# ECU_Sheet6.net
KiCad netlist of a schematic drawn in Altium Designer
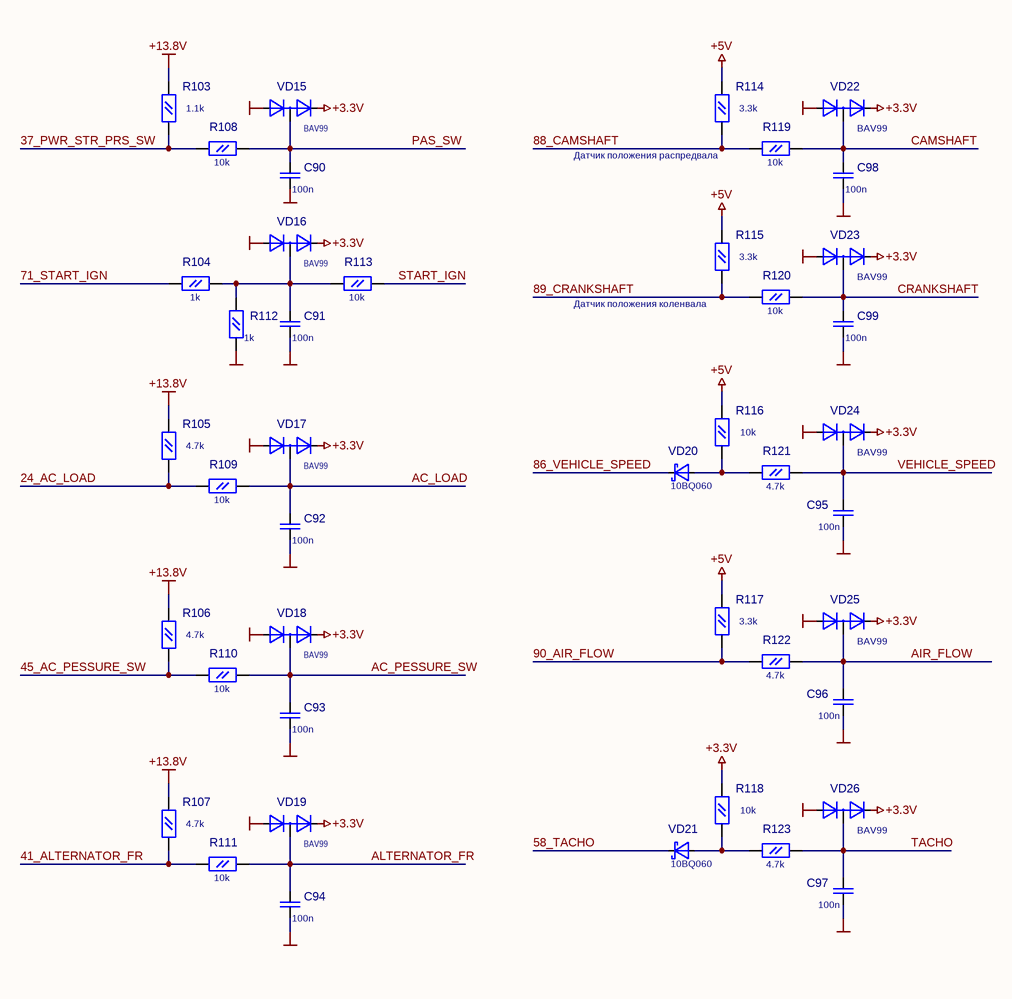
[diagram p0: ECU_Sheet6.SchDoc]

(export (version "E")
  (design (tool "Eeschema 10.0.6"))
  (components
    (comp (ref "C90")
      (value "100n")
      (footprint "C0805L")
      (description "C0603")
      (fields (field (name "Comment") "CSMD"))
      (libsource (lib "L1") (part "CSMD"))
    )
    (comp (ref "C91")
      (value "100n")
      (footprint "C0805L")
      (description "C0603")
      (fields (field (name "Comment") "CSMD"))
      (libsource (lib "L1") (part "CSMD"))
    )
    (comp (ref "C92")
      (value "100n")
      (footprint "C0805L")
      (description "C0603")
      (fields (field (name "Comment") "CSMD"))
      (libsource (lib "L1") (part "CSMD"))
    )
    (comp (ref "C93")
      (value "100n")
      (footprint "C0805L")
      (description "C0603")
      (fields (field (name "Comment") "CSMD"))
      (libsource (lib "L1") (part "CSMD"))
    )
    (comp (ref "C94")
      (value "100n")
      (footprint "C0805L")
      (description "C0603")
      (fields (field (name "Comment") "CSMD"))
      (libsource (lib "L1") (part "CSMD"))
    )
    (comp (ref "C95")
      (value "100n")
      (footprint "C0805L")
      (description "C0603")
      (fields (field (name "Comment") "CSMD"))
      (libsource (lib "L1") (part "CSMD"))
    )
    (comp (ref "C96")
      (value "100n")
      (footprint "C0805L")
      (description "C0603")
      (fields (field (name "Comment") "CSMD"))
      (libsource (lib "L1") (part "CSMD"))
    )
    (comp (ref "C97")
      (value "100n")
      (footprint "C0805L")
      (description "C0603")
      (fields (field (name "Comment") "CSMD"))
      (libsource (lib "L1") (part "CSMD"))
    )
    (comp (ref "C98")
      (value "100n")
      (footprint "C0805L")
      (description "C0603")
      (fields (field (name "Comment") "CSMD"))
      (libsource (lib "L1") (part "CSMD"))
    )
    (comp (ref "C99")
      (value "100n")
      (footprint "C0805L")
      (description "C0603")
      (fields (field (name "Comment") "CSMD"))
      (libsource (lib "L1") (part "CSMD"))
    )
    (comp (ref "R103")
      (value "1.1k")
      (footprint "R0805L")
      (description "R0805")
      (fields (field (name "Comment") "RSMD"))
      (libsource (lib "L1") (part "RSMD"))
    )
    (comp (ref "R104")
      (value "1k")
      (footprint "R0805L")
      (description "R0805")
      (fields (field (name "Comment") "RSMD"))
      (libsource (lib "L1") (part "RSMD"))
    )
    (comp (ref "R105")
      (value "4.7k")
      (footprint "R0805L")
      (description "R0805")
      (fields (field (name "Comment") "RSMD"))
      (libsource (lib "L1") (part "RSMD"))
    )
    (comp (ref "R106")
      (value "4.7k")
      (footprint "R0805L")
      (description "R0805")
      (fields (field (name "Comment") "RSMD"))
      (libsource (lib "L1") (part "RSMD"))
    )
    (comp (ref "R107")
      (value "4.7k")
      (footprint "R0805L")
      (description "R0805")
      (fields (field (name "Comment") "RSMD"))
      (libsource (lib "L1") (part "RSMD"))
    )
    (comp (ref "R108")
      (value "10k")
      (footprint "R0805L")
      (description "R0805")
      (fields (field (name "Comment") "RSMD"))
      (libsource (lib "L1") (part "RSMD"))
    )
    (comp (ref "R109")
      (value "10k")
      (footprint "R0805L")
      (description "R0805")
      (fields (field (name "Comment") "RSMD"))
      (libsource (lib "L1") (part "RSMD"))
    )
    (comp (ref "R110")
      (value "10k")
      (footprint "R0805L")
      (description "R0805")
      (fields (field (name "Comment") "RSMD"))
      (libsource (lib "L1") (part "RSMD"))
    )
    (comp (ref "R111")
      (value "10k")
      (footprint "R0805L")
      (description "R0805")
      (fields (field (name "Comment") "RSMD"))
      (libsource (lib "L1") (part "RSMD"))
    )
    (comp (ref "R112")
      (value "1k")
      (footprint "R0805L")
      (description "R0805")
      (fields (field (name "Comment") "RSMD"))
      (libsource (lib "L1") (part "RSMD"))
    )
    (comp (ref "R113")
      (value "10k")
      (footprint "R0805L")
      (description "R0805")
      (fields (field (name "Comment") "RSMD"))
      (libsource (lib "L1") (part "RSMD"))
    )
    (comp (ref "R114")
      (value "3.3k")
      (footprint "R0805L")
      (description "R0805")
      (fields (field (name "Comment") "RSMD"))
      (libsource (lib "L1") (part "RSMD"))
    )
    (comp (ref "R115")
      (value "3.3k")
      (footprint "R0805L")
      (description "R0805")
      (fields (field (name "Comment") "RSMD"))
      (libsource (lib "L1") (part "RSMD"))
    )
    (comp (ref "R116")
      (value "10k")
      (footprint "R0805L")
      (description "R0805")
      (fields (field (name "Comment") "RSMD"))
      (libsource (lib "L1") (part "RSMD"))
    )
    (comp (ref "R117")
      (value "3.3k")
      (footprint "R0805L")
      (description "R0805")
      (fields (field (name "Comment") "RSMD"))
      (libsource (lib "L1") (part "RSMD"))
    )
    (comp (ref "R118")
      (value "10k")
      (footprint "R0805L")
      (description "R0805")
      (fields (field (name "Comment") "RSMD"))
      (libsource (lib "L1") (part "RSMD"))
    )
    (comp (ref "R119")
      (value "10k")
      (footprint "R0805L")
      (description "R0805")
      (fields (field (name "Comment") "RSMD"))
      (libsource (lib "L1") (part "RSMD"))
    )
    (comp (ref "R120")
      (value "10k")
      (footprint "R0805L")
      (description "R0805")
      (fields (field (name "Comment") "RSMD"))
      (libsource (lib "L1") (part "RSMD"))
    )
    (comp (ref "R121")
      (value "4.7k")
      (footprint "R0805L")
      (description "R0805")
      (fields (field (name "Comment") "RSMD"))
      (libsource (lib "L1") (part "RSMD"))
    )
    (comp (ref "R122")
      (value "4.7k")
      (footprint "R0805L")
      (description "R0805")
      (fields (field (name "Comment") "RSMD"))
      (libsource (lib "L1") (part "RSMD"))
    )
    (comp (ref "R123")
      (value "4.7k")
      (footprint "R0805L")
      (description "R0805")
      (fields (field (name "Comment") "RSMD"))
      (libsource (lib "L1") (part "RSMD"))
    )
    (comp (ref "VD15") (value "BAV99") (footprint "SOT-23") (libsource (lib "RL1") (part "BAV99")))
    (comp (ref "VD16") (value "BAV99") (footprint "SOT-23") (libsource (lib "RL1") (part "BAV99")))
    (comp (ref "VD17") (value "BAV99") (footprint "SOT-23") (libsource (lib "RL1") (part "BAV99")))
    (comp (ref "VD18") (value "BAV99") (footprint "SOT-23") (libsource (lib "RL1") (part "BAV99")))
    (comp (ref "VD19") (value "BAV99") (footprint "SOT-23") (libsource (lib "RL1") (part "BAV99")))
    (comp (ref "VD20")
      (value "10BQ060")
      (footprint "RL1:DO-214AA SMB")
      (libsource (lib "RL1") (part "10BQ060"))
    )
    (comp (ref "VD21")
      (value "10BQ060")
      (footprint "RL1:DO-214AA SMB")
      (libsource (lib "RL1") (part "10BQ060"))
    )
    (comp (ref "VD22") (value "BAV99") (footprint "SOT-23") (libsource (lib "RL1") (part "BAV99")))
    (comp (ref "VD23") (value "BAV99") (footprint "SOT-23") (libsource (lib "RL1") (part "BAV99")))
    (comp (ref "VD24") (value "BAV99") (footprint "SOT-23") (libsource (lib "RL1") (part "BAV99")))
    (comp (ref "VD25") (value "BAV99") (footprint "SOT-23") (libsource (lib "RL1") (part "BAV99")))
    (comp (ref "VD26") (value "BAV99") (footprint "SOT-23") (libsource (lib "RL1") (part "BAV99")))
  )
  (nets
    (net (code "1") (name "+3.3V") (class "Default")
      (node (ref "R118") (pin "2") (pinfunction "Pin2_2") (pintype "passive"))
      (node (ref "VD15") (pin "2") (pinfunction "K_2") (pintype "passive"))
      (node (ref "VD16") (pin "2") (pinfunction "K_2") (pintype "passive"))
      (node (ref "VD17") (pin "2") (pinfunction "K_2") (pintype "passive"))
      (node (ref "VD18") (pin "2") (pinfunction "K_2") (pintype "passive"))
      (node (ref "VD19") (pin "2") (pinfunction "K_2") (pintype "passive"))
      (node (ref "VD22") (pin "2") (pinfunction "K_2") (pintype "passive"))
      (node (ref "VD23") (pin "2") (pinfunction "K_2") (pintype "passive"))
      (node (ref "VD24") (pin "2") (pinfunction "K_2") (pintype "passive"))
      (node (ref "VD25") (pin "2") (pinfunction "K_2") (pintype "passive"))
      (node (ref "VD26") (pin "2") (pinfunction "K_2") (pintype "passive"))
    )
    (net (code "2") (name "+5V") (class "Default")
      (node (ref "R114") (pin "2") (pinfunction "Pin2_2") (pintype "passive"))
      (node (ref "R115") (pin "2") (pinfunction "Pin2_2") (pintype "passive"))
      (node (ref "R116") (pin "2") (pinfunction "Pin2_2") (pintype "passive"))
      (node (ref "R117") (pin "2") (pinfunction "Pin2_2") (pintype "passive"))
    )
    (net (code "3") (name "+13.8V") (class "Default")
      (node (ref "R103") (pin "2") (pinfunction "Pin2_2") (pintype "passive"))
      (node (ref "R105") (pin "2") (pinfunction "Pin2_2") (pintype "passive"))
      (node (ref "R106") (pin "2") (pinfunction "Pin2_2") (pintype "passive"))
      (node (ref "R107") (pin "2") (pinfunction "Pin2_2") (pintype "passive"))
    )
    (net (code "4") (name "/24_AC_LOAD") (class "Default")
      (node (ref "R105") (pin "1") (pinfunction "Pin1_1") (pintype "passive"))
      (node (ref "R109") (pin "1") (pinfunction "Pin1_1") (pintype "passive"))
    )
    (net (code "5") (name "/37_PWR_STR_PRS_SW") (class "Default")
      (node (ref "R103") (pin "1") (pinfunction "Pin1_1") (pintype "passive"))
      (node (ref "R108") (pin "1") (pinfunction "Pin1_1") (pintype "passive"))
    )
    (net (code "6") (name "/41_ALTERNATOR_FR") (class "Default")
      (node (ref "R107") (pin "1") (pinfunction "Pin1_1") (pintype "passive"))
      (node (ref "R111") (pin "1") (pinfunction "Pin1_1") (pintype "passive"))
    )
    (net (code "7") (name "/45_AC_PESSURE_SW") (class "Default")
      (node (ref "R106") (pin "1") (pinfunction "Pin1_1") (pintype "passive"))
      (node (ref "R110") (pin "1") (pinfunction "Pin1_1") (pintype "passive"))
    )
    (net (code "8") (name "/58_TACHO") (class "Default") (node (ref "VD21") (pin "2") (pintype "passive")))
    (net (code "9") (name "/71_START_IGN") (class "Default")
      (node (ref "R104") (pin "1") (pinfunction "Pin1_1") (pintype "passive"))
    )
    (net (code "10") (name "/86_VEHICLE_SPEED") (class "Default")
      (node (ref "VD20") (pin "2") (pintype "passive"))
    )
    (net (code "11") (name "/88_CAMSHAFT") (class "Default")
      (node (ref "R114") (pin "1") (pinfunction "Pin1_1") (pintype "passive"))
      (node (ref "R119") (pin "1") (pinfunction "Pin1_1") (pintype "passive"))
    )
    (net (code "12") (name "/89_CRANKSHAFT") (class "Default")
      (node (ref "R115") (pin "1") (pinfunction "Pin1_1") (pintype "passive"))
      (node (ref "R120") (pin "1") (pinfunction "Pin1_1") (pintype "passive"))
    )
    (net (code "13") (name "/90_AIR_FLOW") (class "Default")
      (node (ref "R117") (pin "1") (pinfunction "Pin1_1") (pintype "passive"))
      (node (ref "R122") (pin "1") (pinfunction "Pin1_1") (pintype "passive"))
    )
    (net (code "14") (name "/AC_LOAD") (class "Default")
      (node (ref "C92") (pin "1") (pintype "passive"))
      (node (ref "R109") (pin "2") (pinfunction "Pin2_2") (pintype "passive"))
      (node (ref "VD17") (pin "3") (pinfunction "C_3") (pintype "passive"))
    )
    (net (code "15") (name "/AC_PESSURE_SW") (class "Default")
      (node (ref "C93") (pin "1") (pintype "passive"))
      (node (ref "R110") (pin "2") (pinfunction "Pin2_2") (pintype "passive"))
      (node (ref "VD18") (pin "3") (pinfunction "C_3") (pintype "passive"))
    )
    (net (code "16") (name "/AIR_FLOW") (class "Default")
      (node (ref "C96") (pin "1") (pintype "passive"))
      (node (ref "R122") (pin "2") (pinfunction "Pin2_2") (pintype "passive"))
      (node (ref "VD25") (pin "3") (pinfunction "C_3") (pintype "passive"))
    )
    (net (code "17") (name "/ALTERNATOR_FR") (class "Default")
      (node (ref "C94") (pin "1") (pintype "passive"))
      (node (ref "R111") (pin "2") (pinfunction "Pin2_2") (pintype "passive"))
      (node (ref "VD19") (pin "3") (pinfunction "C_3") (pintype "passive"))
    )
    (net (code "18") (name "/CAMSHAFT") (class "Default")
      (node (ref "C98") (pin "1") (pintype "passive"))
      (node (ref "R119") (pin "2") (pinfunction "Pin2_2") (pintype "passive"))
      (node (ref "VD22") (pin "3") (pinfunction "C_3") (pintype "passive"))
    )
    (net (code "19") (name "/CRANKSHAFT") (class "Default")
      (node (ref "C99") (pin "1") (pintype "passive"))
      (node (ref "R120") (pin "2") (pinfunction "Pin2_2") (pintype "passive"))
      (node (ref "VD23") (pin "3") (pinfunction "C_3") (pintype "passive"))
    )
    (net (code "20") (name "/PAS_SW") (class "Default")
      (node (ref "C90") (pin "1") (pintype "passive"))
      (node (ref "R108") (pin "2") (pinfunction "Pin2_2") (pintype "passive"))
      (node (ref "VD15") (pin "3") (pinfunction "C_3") (pintype "passive"))
    )
    (net (code "21") (name "/START_IGN") (class "Default")
      (node (ref "R113") (pin "2") (pinfunction "Pin2_2") (pintype "passive"))
    )
    (net (code "22") (name "/TACHO") (class "Default")
      (node (ref "C97") (pin "1") (pintype "passive"))
      (node (ref "R123") (pin "2") (pinfunction "Pin2_2") (pintype "passive"))
      (node (ref "VD26") (pin "3") (pinfunction "C_3") (pintype "passive"))
    )
    (net (code "23") (name "/VEHICLE_SPEED") (class "Default")
      (node (ref "C95") (pin "1") (pintype "passive"))
      (node (ref "R121") (pin "2") (pinfunction "Pin2_2") (pintype "passive"))
      (node (ref "VD24") (pin "3") (pinfunction "C_3") (pintype "passive"))
    )
    (net (code "24") (name "GND") (class "Default")
      (node (ref "C90") (pin "2") (pintype "passive"))
      (node (ref "C91") (pin "2") (pintype "passive"))
      (node (ref "C92") (pin "2") (pintype "passive"))
      (node (ref "C93") (pin "2") (pintype "passive"))
      (node (ref "C94") (pin "2") (pintype "passive"))
      (node (ref "C95") (pin "2") (pintype "passive"))
      (node (ref "C96") (pin "2") (pintype "passive"))
      (node (ref "C97") (pin "2") (pintype "passive"))
      (node (ref "C98") (pin "2") (pintype "passive"))
      (node (ref "C99") (pin "2") (pintype "passive"))
      (node (ref "R112") (pin "1") (pinfunction "Pin1_1") (pintype "passive"))
      (node (ref "VD15") (pin "1") (pinfunction "A_1") (pintype "passive"))
      (node (ref "VD16") (pin "1") (pinfunction "A_1") (pintype "passive"))
      (node (ref "VD17") (pin "1") (pinfunction "A_1") (pintype "passive"))
      (node (ref "VD18") (pin "1") (pinfunction "A_1") (pintype "passive"))
      (node (ref "VD19") (pin "1") (pinfunction "A_1") (pintype "passive"))
      (node (ref "VD22") (pin "1") (pinfunction "A_1") (pintype "passive"))
      (node (ref "VD23") (pin "1") (pinfunction "A_1") (pintype "passive"))
      (node (ref "VD24") (pin "1") (pinfunction "A_1") (pintype "passive"))
      (node (ref "VD25") (pin "1") (pinfunction "A_1") (pintype "passive"))
      (node (ref "VD26") (pin "1") (pinfunction "A_1") (pintype "passive"))
    )
    (net (code "25") (name "Net-(R104-Pin2)") (class "Default")
      (node (ref "C91") (pin "1") (pintype "passive"))
      (node (ref "R104") (pin "2") (pinfunction "Pin2_2") (pintype "passive"))
      (node (ref "R112") (pin "2") (pinfunction "Pin2_2") (pintype "passive"))
      (node (ref "R113") (pin "1") (pinfunction "Pin1_1") (pintype "passive"))
      (node (ref "VD16") (pin "3") (pinfunction "C_3") (pintype "passive"))
    )
    (net (code "26") (name "Net-(R116-Pin1)") (class "Default")
      (node (ref "R116") (pin "1") (pinfunction "Pin1_1") (pintype "passive"))
      (node (ref "R121") (pin "1") (pinfunction "Pin1_1") (pintype "passive"))
      (node (ref "VD20") (pin "1") (pintype "passive"))
    )
    (net (code "27") (name "Net-(R118-Pin1)") (class "Default")
      (node (ref "R118") (pin "1") (pinfunction "Pin1_1") (pintype "passive"))
      (node (ref "R123") (pin "1") (pinfunction "Pin1_1") (pintype "passive"))
      (node (ref "VD21") (pin "1") (pintype "passive"))
    )
  )
)
